# 8OR_1.net
KiCad netlist of a schematic drawn in EAGLE
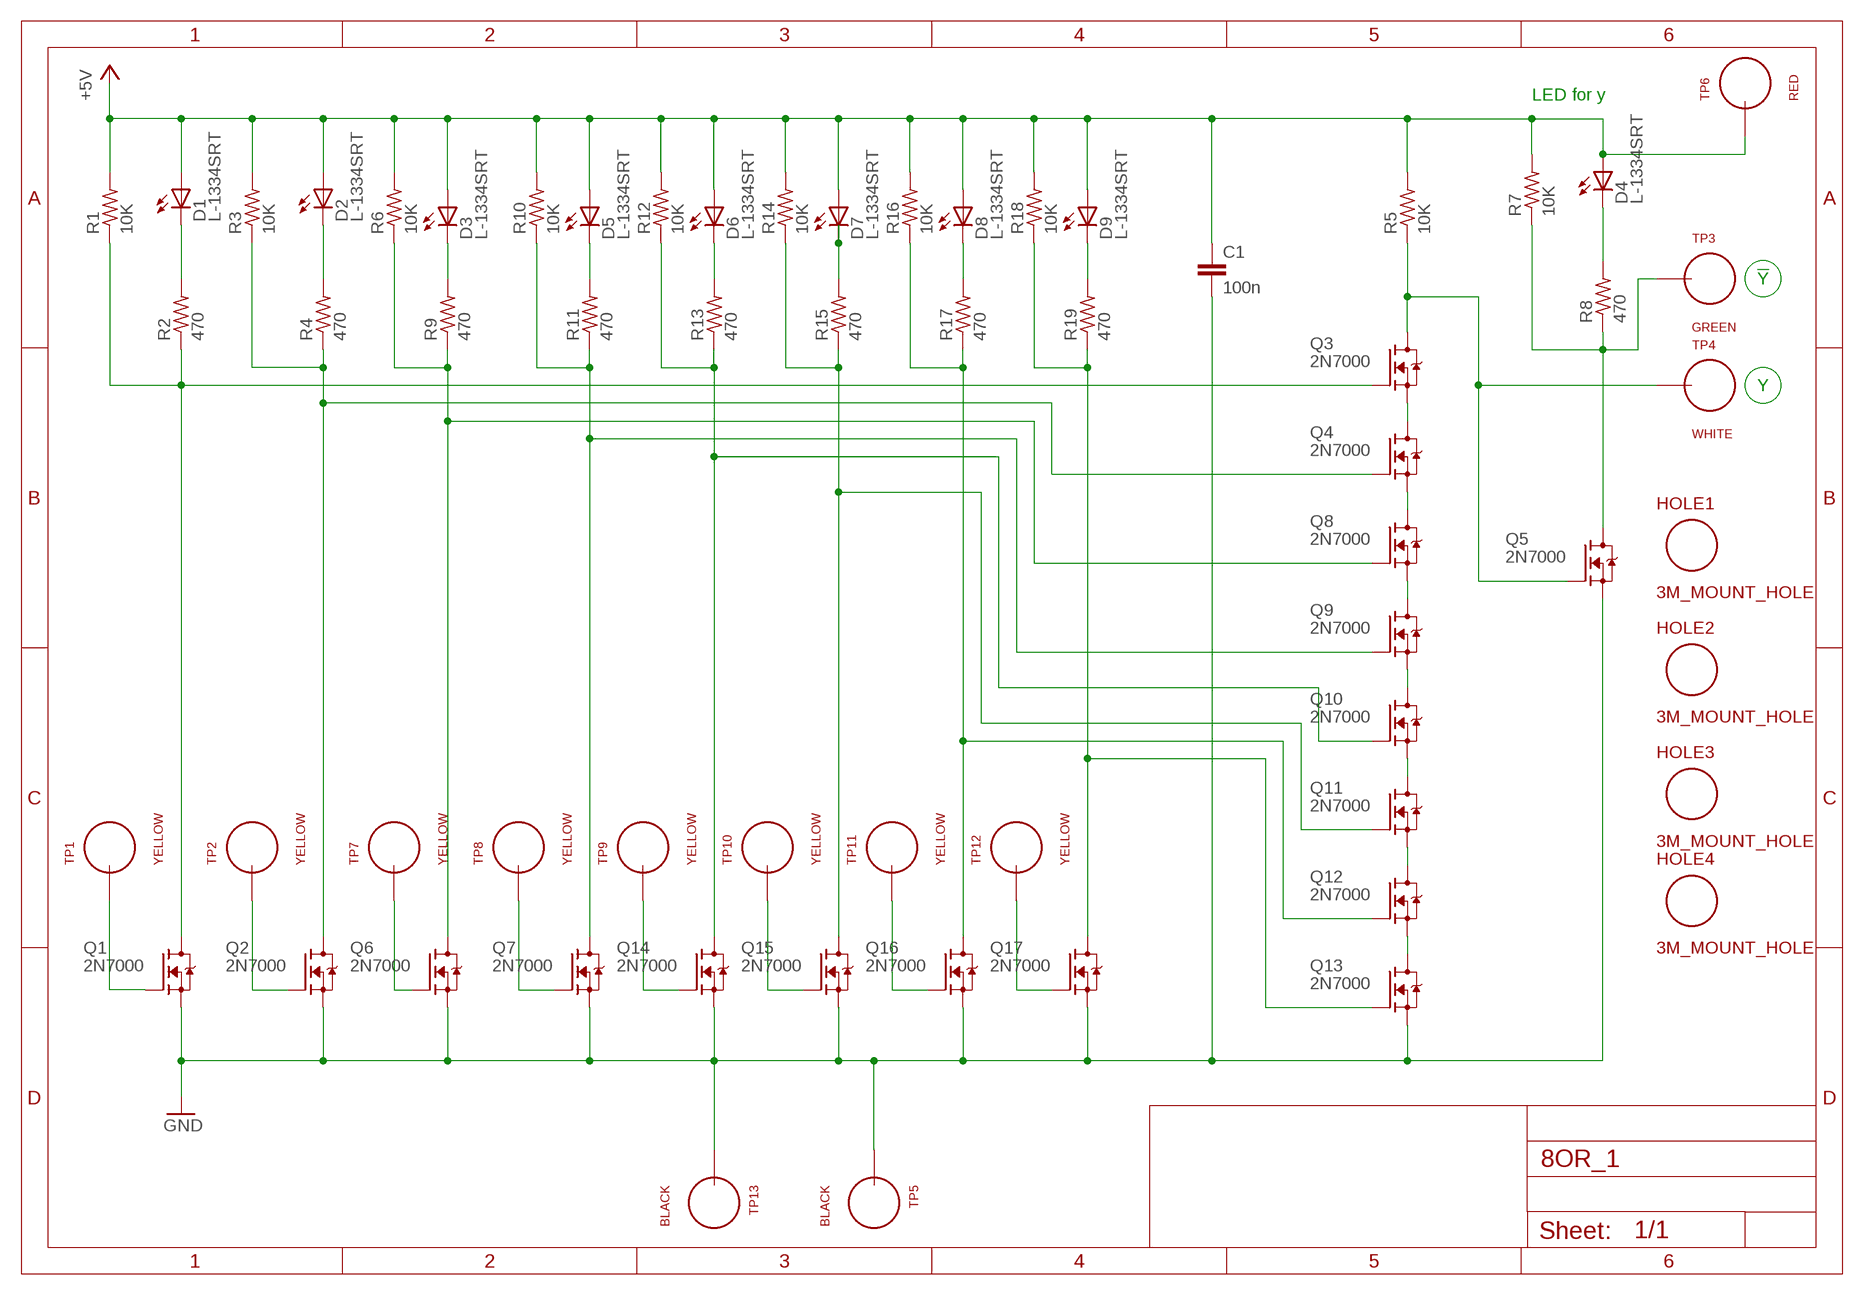
[diagram p0: schematic, sheet 1]

(export (version "E")
  (design (tool "Eeschema 10.0.6"))
  (components
    (comp (ref "C1")
      (value "100n")
      (footprint "eagle-import:CAP_P2INCH")
      (libsource (lib "eagle-import") (part "C_P2INCH"))
    )
    (comp (ref "D1")
      (value "L-1334SRT")
      (footprint "eagle-import:LED3MM")
      (libsource (lib "eagle-import") (part "L-1334SRT"))
    )
    (comp (ref "D2")
      (value "L-1334SRT")
      (footprint "eagle-import:LED3MM")
      (libsource (lib "eagle-import") (part "L-1334SRT"))
    )
    (comp (ref "D3")
      (value "L-1334SRT")
      (footprint "eagle-import:LED3MM")
      (libsource (lib "eagle-import") (part "L-1334SRT"))
    )
    (comp (ref "D4")
      (value "L-1334SRT")
      (footprint "eagle-import:LED3MM")
      (libsource (lib "eagle-import") (part "L-1334SRT"))
    )
    (comp (ref "D5")
      (value "L-1334SRT")
      (footprint "eagle-import:LED3MM")
      (libsource (lib "eagle-import") (part "L-1334SRT"))
    )
    (comp (ref "D6")
      (value "L-1334SRT")
      (footprint "eagle-import:LED3MM")
      (libsource (lib "eagle-import") (part "L-1334SRT"))
    )
    (comp (ref "D7")
      (value "L-1334SRT")
      (footprint "eagle-import:LED3MM")
      (libsource (lib "eagle-import") (part "L-1334SRT"))
    )
    (comp (ref "D8")
      (value "L-1334SRT")
      (footprint "eagle-import:LED3MM")
      (libsource (lib "eagle-import") (part "L-1334SRT"))
    )
    (comp (ref "D9")
      (value "L-1334SRT")
      (footprint "eagle-import:LED3MM")
      (libsource (lib "eagle-import") (part "L-1334SRT"))
    )
    (comp (ref "HOLE1")
      (value "3M_MOUNT_HOLE")
      (footprint "eagle-import:3M_HOLE")
      (libsource (lib "eagle-import") (part "3M_MOUNT_HOLE"))
    )
    (comp (ref "HOLE2")
      (value "3M_MOUNT_HOLE")
      (footprint "eagle-import:3M_HOLE")
      (libsource (lib "eagle-import") (part "3M_MOUNT_HOLE"))
    )
    (comp (ref "HOLE3")
      (value "3M_MOUNT_HOLE")
      (footprint "eagle-import:3M_HOLE")
      (libsource (lib "eagle-import") (part "3M_MOUNT_HOLE"))
    )
    (comp (ref "HOLE4")
      (value "3M_MOUNT_HOLE")
      (footprint "eagle-import:3M_HOLE")
      (libsource (lib "eagle-import") (part "3M_MOUNT_HOLE"))
    )
    (comp (ref "Q1")
      (value "2N7000")
      (footprint "eagle-import:TO92-DGS")
      (libsource (lib "eagle-import") (part "2N7000"))
    )
    (comp (ref "Q2")
      (value "2N7000")
      (footprint "eagle-import:TO92-DGS")
      (libsource (lib "eagle-import") (part "2N7000"))
    )
    (comp (ref "Q3")
      (value "2N7000")
      (footprint "eagle-import:TO92-DGS")
      (libsource (lib "eagle-import") (part "2N7000"))
    )
    (comp (ref "Q4")
      (value "2N7000")
      (footprint "eagle-import:TO92-DGS")
      (libsource (lib "eagle-import") (part "2N7000"))
    )
    (comp (ref "Q5")
      (value "2N7000")
      (footprint "eagle-import:TO92-DGS")
      (libsource (lib "eagle-import") (part "2N7000"))
    )
    (comp (ref "Q6")
      (value "2N7000")
      (footprint "eagle-import:TO92-DGS")
      (libsource (lib "eagle-import") (part "2N7000"))
    )
    (comp (ref "Q7")
      (value "2N7000")
      (footprint "eagle-import:TO92-DGS")
      (libsource (lib "eagle-import") (part "2N7000"))
    )
    (comp (ref "Q8")
      (value "2N7000")
      (footprint "eagle-import:TO92-DGS")
      (libsource (lib "eagle-import") (part "2N7000"))
    )
    (comp (ref "Q9")
      (value "2N7000")
      (footprint "eagle-import:TO92-DGS")
      (libsource (lib "eagle-import") (part "2N7000"))
    )
    (comp (ref "Q10")
      (value "2N7000")
      (footprint "eagle-import:TO92-DGS")
      (libsource (lib "eagle-import") (part "2N7000"))
    )
    (comp (ref "Q11")
      (value "2N7000")
      (footprint "eagle-import:TO92-DGS")
      (libsource (lib "eagle-import") (part "2N7000"))
    )
    (comp (ref "Q12")
      (value "2N7000")
      (footprint "eagle-import:TO92-DGS")
      (libsource (lib "eagle-import") (part "2N7000"))
    )
    (comp (ref "Q13")
      (value "2N7000")
      (footprint "eagle-import:TO92-DGS")
      (libsource (lib "eagle-import") (part "2N7000"))
    )
    (comp (ref "Q14")
      (value "2N7000")
      (footprint "eagle-import:TO92-DGS")
      (libsource (lib "eagle-import") (part "2N7000"))
    )
    (comp (ref "Q15")
      (value "2N7000")
      (footprint "eagle-import:TO92-DGS")
      (libsource (lib "eagle-import") (part "2N7000"))
    )
    (comp (ref "Q16")
      (value "2N7000")
      (footprint "eagle-import:TO92-DGS")
      (libsource (lib "eagle-import") (part "2N7000"))
    )
    (comp (ref "Q17")
      (value "2N7000")
      (footprint "eagle-import:TO92-DGS")
      (libsource (lib "eagle-import") (part "2N7000"))
    )
    (comp (ref "R1")
      (value "10K")
      (footprint "eagle-import:R_P2INCH")
      (libsource (lib "eagle-import") (part "R_P2INCH"))
    )
    (comp (ref "R2")
      (value "470")
      (footprint "eagle-import:R_P2INCH")
      (libsource (lib "eagle-import") (part "R_P2INCH"))
    )
    (comp (ref "R3")
      (value "10K")
      (footprint "eagle-import:R_P2INCH")
      (libsource (lib "eagle-import") (part "R_P2INCH"))
    )
    (comp (ref "R4")
      (value "470")
      (footprint "eagle-import:R_P2INCH")
      (libsource (lib "eagle-import") (part "R_P2INCH"))
    )
    (comp (ref "R5")
      (value "10K")
      (footprint "eagle-import:R_P2INCH")
      (libsource (lib "eagle-import") (part "R_P2INCH"))
    )
    (comp (ref "R6")
      (value "10K")
      (footprint "eagle-import:R_P2INCH")
      (libsource (lib "eagle-import") (part "R_P2INCH"))
    )
    (comp (ref "R7")
      (value "10K")
      (footprint "eagle-import:R_P2INCH")
      (libsource (lib "eagle-import") (part "R_P2INCH"))
    )
    (comp (ref "R8")
      (value "470")
      (footprint "eagle-import:R_P2INCH")
      (libsource (lib "eagle-import") (part "R_P2INCH"))
    )
    (comp (ref "R9")
      (value "470")
      (footprint "eagle-import:R_P2INCH")
      (libsource (lib "eagle-import") (part "R_P2INCH"))
    )
    (comp (ref "R10")
      (value "10K")
      (footprint "eagle-import:R_P2INCH")
      (libsource (lib "eagle-import") (part "R_P2INCH"))
    )
    (comp (ref "R11")
      (value "470")
      (footprint "eagle-import:R_P2INCH")
      (libsource (lib "eagle-import") (part "R_P2INCH"))
    )
    (comp (ref "R12")
      (value "10K")
      (footprint "eagle-import:R_P2INCH")
      (libsource (lib "eagle-import") (part "R_P2INCH"))
    )
    (comp (ref "R13")
      (value "470")
      (footprint "eagle-import:R_P2INCH")
      (libsource (lib "eagle-import") (part "R_P2INCH"))
    )
    (comp (ref "R14")
      (value "10K")
      (footprint "eagle-import:R_P2INCH")
      (libsource (lib "eagle-import") (part "R_P2INCH"))
    )
    (comp (ref "R15")
      (value "470")
      (footprint "eagle-import:R_P2INCH")
      (libsource (lib "eagle-import") (part "R_P2INCH"))
    )
    (comp (ref "R16")
      (value "10K")
      (footprint "eagle-import:R_P2INCH")
      (libsource (lib "eagle-import") (part "R_P2INCH"))
    )
    (comp (ref "R17")
      (value "470")
      (footprint "eagle-import:R_P2INCH")
      (libsource (lib "eagle-import") (part "R_P2INCH"))
    )
    (comp (ref "R18")
      (value "10K")
      (footprint "eagle-import:R_P2INCH")
      (libsource (lib "eagle-import") (part "R_P2INCH"))
    )
    (comp (ref "R19")
      (value "470")
      (footprint "eagle-import:R_P2INCH")
      (libsource (lib "eagle-import") (part "R_P2INCH"))
    )
    (comp (ref "TP1")
      (value "YELLOW")
      (footprint "eagle-import:TEST_LOOP")
      (libsource (lib "eagle-import") (part "TEST_LOOP"))
    )
    (comp (ref "TP2")
      (value "YELLOW")
      (footprint "eagle-import:TEST_LOOP")
      (libsource (lib "eagle-import") (part "TEST_LOOP"))
    )
    (comp (ref "TP3")
      (value "GREEN")
      (footprint "eagle-import:TEST_LOOP")
      (libsource (lib "eagle-import") (part "TEST_LOOP"))
    )
    (comp (ref "TP4")
      (value "WHITE")
      (footprint "eagle-import:TEST_LOOP")
      (libsource (lib "eagle-import") (part "TEST_LOOP"))
    )
    (comp (ref "TP5")
      (value "BLACK")
      (footprint "eagle-import:TEST_LOOP")
      (libsource (lib "eagle-import") (part "TEST_LOOP"))
    )
    (comp (ref "TP6")
      (value "RED")
      (footprint "eagle-import:TEST_LOOP")
      (libsource (lib "eagle-import") (part "TEST_LOOP"))
    )
    (comp (ref "TP7")
      (value "YELLOW")
      (footprint "eagle-import:TEST_LOOP")
      (libsource (lib "eagle-import") (part "TEST_LOOP"))
    )
    (comp (ref "TP8")
      (value "YELLOW")
      (footprint "eagle-import:TEST_LOOP")
      (libsource (lib "eagle-import") (part "TEST_LOOP"))
    )
    (comp (ref "TP9")
      (value "YELLOW")
      (footprint "eagle-import:TEST_LOOP")
      (libsource (lib "eagle-import") (part "TEST_LOOP"))
    )
    (comp (ref "TP10")
      (value "YELLOW")
      (footprint "eagle-import:TEST_LOOP")
      (libsource (lib "eagle-import") (part "TEST_LOOP"))
    )
    (comp (ref "TP11")
      (value "YELLOW")
      (footprint "eagle-import:TEST_LOOP")
      (libsource (lib "eagle-import") (part "TEST_LOOP"))
    )
    (comp (ref "TP12")
      (value "YELLOW")
      (footprint "eagle-import:TEST_LOOP")
      (libsource (lib "eagle-import") (part "TEST_LOOP"))
    )
    (comp (ref "TP13")
      (value "BLACK")
      (footprint "eagle-import:TEST_LOOP")
      (libsource (lib "eagle-import") (part "TEST_LOOP"))
    )
  )
  (nets
    (net (code "1") (name "+5V") (class "Default")
      (node (ref "C1") (pin "1") (pinfunction "1_1") (pintype "passive"))
      (node (ref "D1") (pin "A") (pinfunction "A_A") (pintype "passive"))
      (node (ref "D2") (pin "A") (pinfunction "A_A") (pintype "passive"))
      (node (ref "D3") (pin "A") (pinfunction "A_A") (pintype "passive"))
      (node (ref "D4") (pin "A") (pinfunction "A_A") (pintype "passive"))
      (node (ref "D5") (pin "A") (pinfunction "A_A") (pintype "passive"))
      (node (ref "D6") (pin "A") (pinfunction "A_A") (pintype "passive"))
      (node (ref "D7") (pin "A") (pinfunction "A_A") (pintype "passive"))
      (node (ref "D8") (pin "A") (pinfunction "A_A") (pintype "passive"))
      (node (ref "D9") (pin "A") (pinfunction "A_A") (pintype "passive"))
      (node (ref "R1") (pin "2") (pinfunction "2_2") (pintype "passive"))
      (node (ref "R10") (pin "2") (pinfunction "2_2") (pintype "passive"))
      (node (ref "R12") (pin "2") (pinfunction "2_2") (pintype "passive"))
      (node (ref "R14") (pin "2") (pinfunction "2_2") (pintype "passive"))
      (node (ref "R16") (pin "2") (pinfunction "2_2") (pintype "passive"))
      (node (ref "R18") (pin "2") (pinfunction "2_2") (pintype "passive"))
      (node (ref "R3") (pin "2") (pinfunction "2_2") (pintype "passive"))
      (node (ref "R5") (pin "2") (pinfunction "2_2") (pintype "passive"))
      (node (ref "R6") (pin "2") (pinfunction "2_2") (pintype "passive"))
      (node (ref "R7") (pin "2") (pinfunction "2_2") (pintype "passive"))
      (node (ref "TP6") (pin "P$1") (pinfunction "P$1_P$1") (pintype "bidirectional"))
    )
    (net (code "2") (name "GND") (class "Default")
      (node (ref "C1") (pin "2") (pinfunction "2_2") (pintype "passive"))
      (node (ref "Q1") (pin "S") (pinfunction "S_S") (pintype "passive"))
      (node (ref "Q13") (pin "S") (pinfunction "S_S") (pintype "passive"))
      (node (ref "Q14") (pin "S") (pinfunction "S_S") (pintype "passive"))
      (node (ref "Q15") (pin "S") (pinfunction "S_S") (pintype "passive"))
      (node (ref "Q16") (pin "S") (pinfunction "S_S") (pintype "passive"))
      (node (ref "Q17") (pin "S") (pinfunction "S_S") (pintype "passive"))
      (node (ref "Q2") (pin "S") (pinfunction "S_S") (pintype "passive"))
      (node (ref "Q5") (pin "S") (pinfunction "S_S") (pintype "passive"))
      (node (ref "Q6") (pin "S") (pinfunction "S_S") (pintype "passive"))
      (node (ref "Q7") (pin "S") (pinfunction "S_S") (pintype "passive"))
      (node (ref "TP13") (pin "P$1") (pinfunction "P$1_P$1") (pintype "bidirectional"))
      (node (ref "TP5") (pin "P$1") (pinfunction "P$1_P$1") (pintype "bidirectional"))
    )
    (net (code "3") (name "Net-(D1-C)") (class "Default")
      (node (ref "D1") (pin "K") (pinfunction "C_K") (pintype "passive"))
      (node (ref "R2") (pin "2") (pinfunction "2_2") (pintype "passive"))
    )
    (net (code "4") (name "Net-(D2-C)") (class "Default")
      (node (ref "D2") (pin "K") (pinfunction "C_K") (pintype "passive"))
      (node (ref "R4") (pin "2") (pinfunction "2_2") (pintype "passive"))
    )
    (net (code "5") (name "Net-(D3-C)") (class "Default")
      (node (ref "D3") (pin "K") (pinfunction "C_K") (pintype "passive"))
      (node (ref "R9") (pin "2") (pinfunction "2_2") (pintype "passive"))
    )
    (net (code "6") (name "Net-(D4-C)") (class "Default")
      (node (ref "D4") (pin "K") (pinfunction "C_K") (pintype "passive"))
      (node (ref "R8") (pin "2") (pinfunction "2_2") (pintype "passive"))
    )
    (net (code "7") (name "Net-(D5-C)") (class "Default")
      (node (ref "D5") (pin "K") (pinfunction "C_K") (pintype "passive"))
      (node (ref "R11") (pin "2") (pinfunction "2_2") (pintype "passive"))
    )
    (net (code "8") (name "Net-(D6-C)") (class "Default")
      (node (ref "D6") (pin "K") (pinfunction "C_K") (pintype "passive"))
      (node (ref "R13") (pin "2") (pinfunction "2_2") (pintype "passive"))
    )
    (net (code "9") (name "Net-(D7-C)") (class "Default")
      (node (ref "D7") (pin "K") (pinfunction "C_K") (pintype "passive"))
      (node (ref "R15") (pin "2") (pinfunction "2_2") (pintype "passive"))
    )
    (net (code "10") (name "Net-(D8-C)") (class "Default")
      (node (ref "D8") (pin "K") (pinfunction "C_K") (pintype "passive"))
      (node (ref "R17") (pin "2") (pinfunction "2_2") (pintype "passive"))
    )
    (net (code "11") (name "Net-(D9-C)") (class "Default")
      (node (ref "D9") (pin "K") (pinfunction "C_K") (pintype "passive"))
      (node (ref "R19") (pin "2") (pinfunction "2_2") (pintype "passive"))
    )
    (net (code "12") (name "Net-(Q1-PadD)") (class "Default")
      (node (ref "Q1") (pin "D") (pinfunction "D_D") (pintype "passive"))
      (node (ref "Q3") (pin "G") (pinfunction "G_G") (pintype "passive"))
      (node (ref "R1") (pin "1") (pinfunction "1_1") (pintype "passive"))
      (node (ref "R2") (pin "1") (pinfunction "1_1") (pintype "passive"))
    )
    (net (code "13") (name "Net-(Q1-PadG)") (class "Default")
      (node (ref "Q1") (pin "G") (pinfunction "G_G") (pintype "passive"))
      (node (ref "TP1") (pin "P$1") (pinfunction "P$1_P$1") (pintype "bidirectional"))
    )
    (net (code "14") (name "Net-(Q2-PadD)") (class "Default")
      (node (ref "Q2") (pin "D") (pinfunction "D_D") (pintype "passive"))
      (node (ref "Q4") (pin "G") (pinfunction "G_G") (pintype "passive"))
      (node (ref "R3") (pin "1") (pinfunction "1_1") (pintype "passive"))
      (node (ref "R4") (pin "1") (pinfunction "1_1") (pintype "passive"))
    )
    (net (code "15") (name "Net-(Q2-PadG)") (class "Default")
      (node (ref "Q2") (pin "G") (pinfunction "G_G") (pintype "passive"))
      (node (ref "TP2") (pin "P$1") (pinfunction "P$1_P$1") (pintype "bidirectional"))
    )
    (net (code "16") (name "Net-(Q3-PadD)") (class "Default")
      (node (ref "Q3") (pin "D") (pinfunction "D_D") (pintype "passive"))
      (node (ref "Q5") (pin "G") (pinfunction "G_G") (pintype "passive"))
      (node (ref "R5") (pin "1") (pinfunction "1_1") (pintype "passive"))
      (node (ref "TP4") (pin "P$1") (pinfunction "P$1_P$1") (pintype "bidirectional"))
    )
    (net (code "17") (name "Net-(Q3-PadS)") (class "Default")
      (node (ref "Q3") (pin "S") (pinfunction "S_S") (pintype "passive"))
      (node (ref "Q4") (pin "D") (pinfunction "D_D") (pintype "passive"))
    )
    (net (code "18") (name "Net-(Q4-PadS)") (class "Default")
      (node (ref "Q4") (pin "S") (pinfunction "S_S") (pintype "passive"))
      (node (ref "Q8") (pin "D") (pinfunction "D_D") (pintype "passive"))
    )
    (net (code "19") (name "Net-(Q5-PadD)") (class "Default")
      (node (ref "Q5") (pin "D") (pinfunction "D_D") (pintype "passive"))
      (node (ref "R7") (pin "1") (pinfunction "1_1") (pintype "passive"))
      (node (ref "R8") (pin "1") (pinfunction "1_1") (pintype "passive"))
      (node (ref "TP3") (pin "P$1") (pinfunction "P$1_P$1") (pintype "bidirectional"))
    )
    (net (code "20") (name "Net-(Q6-PadD)") (class "Default")
      (node (ref "Q6") (pin "D") (pinfunction "D_D") (pintype "passive"))
      (node (ref "Q8") (pin "G") (pinfunction "G_G") (pintype "passive"))
      (node (ref "R6") (pin "1") (pinfunction "1_1") (pintype "passive"))
      (node (ref "R9") (pin "1") (pinfunction "1_1") (pintype "passive"))
    )
    (net (code "21") (name "Net-(Q6-PadG)") (class "Default")
      (node (ref "Q6") (pin "G") (pinfunction "G_G") (pintype "passive"))
      (node (ref "TP7") (pin "P$1") (pinfunction "P$1_P$1") (pintype "bidirectional"))
    )
    (net (code "22") (name "Net-(Q7-PadD)") (class "Default")
      (node (ref "Q7") (pin "D") (pinfunction "D_D") (pintype "passive"))
      (node (ref "Q9") (pin "G") (pinfunction "G_G") (pintype "passive"))
      (node (ref "R10") (pin "1") (pinfunction "1_1") (pintype "passive"))
      (node (ref "R11") (pin "1") (pinfunction "1_1") (pintype "passive"))
    )
    (net (code "23") (name "Net-(Q7-PadG)") (class "Default")
      (node (ref "Q7") (pin "G") (pinfunction "G_G") (pintype "passive"))
      (node (ref "TP8") (pin "P$1") (pinfunction "P$1_P$1") (pintype "bidirectional"))
    )
    (net (code "24") (name "Net-(Q8-PadS)") (class "Default")
      (node (ref "Q8") (pin "S") (pinfunction "S_S") (pintype "passive"))
      (node (ref "Q9") (pin "D") (pinfunction "D_D") (pintype "passive"))
    )
    (net (code "25") (name "Net-(Q10-PadD)") (class "Default")
      (node (ref "Q10") (pin "D") (pinfunction "D_D") (pintype "passive"))
      (node (ref "Q9") (pin "S") (pinfunction "S_S") (pintype "passive"))
    )
    (net (code "26") (name "Net-(Q10-PadG)") (class "Default")
      (node (ref "Q10") (pin "G") (pinfunction "G_G") (pintype "passive"))
      (node (ref "Q14") (pin "D") (pinfunction "D_D") (pintype "passive"))
      (node (ref "R12") (pin "1") (pinfunction "1_1") (pintype "passive"))
      (node (ref "R13") (pin "1") (pinfunction "1_1") (pintype "passive"))
    )
    (net (code "27") (name "Net-(Q10-PadS)") (class "Default")
      (node (ref "Q10") (pin "S") (pinfunction "S_S") (pintype "passive"))
      (node (ref "Q11") (pin "D") (pinfunction "D_D") (pintype "passive"))
    )
    (net (code "28") (name "Net-(Q11-PadG)") (class "Default")
      (node (ref "Q11") (pin "G") (pinfunction "G_G") (pintype "passive"))
      (node (ref "Q15") (pin "D") (pinfunction "D_D") (pintype "passive"))
      (node (ref "R14") (pin "1") (pinfunction "1_1") (pintype "passive"))
      (node (ref "R15") (pin "1") (pinfunction "1_1") (pintype "passive"))
    )
    (net (code "29") (name "Net-(Q11-PadS)") (class "Default")
      (node (ref "Q11") (pin "S") (pinfunction "S_S") (pintype "passive"))
      (node (ref "Q12") (pin "D") (pinfunction "D_D") (pintype "passive"))
    )
    (net (code "30") (name "Net-(Q12-PadG)") (class "Default")
      (node (ref "Q12") (pin "G") (pinfunction "G_G") (pintype "passive"))
      (node (ref "Q16") (pin "D") (pinfunction "D_D") (pintype "passive"))
      (node (ref "R16") (pin "1") (pinfunction "1_1") (pintype "passive"))
      (node (ref "R17") (pin "1") (pinfunction "1_1") (pintype "passive"))
    )
    (net (code "31") (name "Net-(Q12-PadS)") (class "Default")
      (node (ref "Q12") (pin "S") (pinfunction "S_S") (pintype "passive"))
      (node (ref "Q13") (pin "D") (pinfunction "D_D") (pintype "passive"))
    )
    (net (code "32") (name "Net-(Q13-PadG)") (class "Default")
      (node (ref "Q13") (pin "G") (pinfunction "G_G") (pintype "passive"))
      (node (ref "Q17") (pin "D") (pinfunction "D_D") (pintype "passive"))
      (node (ref "R18") (pin "1") (pinfunction "1_1") (pintype "passive"))
      (node (ref "R19") (pin "1") (pinfunction "1_1") (pintype "passive"))
    )
    (net (code "33") (name "Net-(Q14-PadG)") (class "Default")
      (node (ref "Q14") (pin "G") (pinfunction "G_G") (pintype "passive"))
      (node (ref "TP9") (pin "P$1") (pinfunction "P$1_P$1") (pintype "bidirectional"))
    )
    (net (code "34") (name "Net-(Q15-PadG)") (class "Default")
      (node (ref "Q15") (pin "G") (pinfunction "G_G") (pintype "passive"))
      (node (ref "TP10") (pin "P$1") (pinfunction "P$1_P$1") (pintype "bidirectional"))
    )
    (net (code "35") (name "Net-(Q16-PadG)") (class "Default")
      (node (ref "Q16") (pin "G") (pinfunction "G_G") (pintype "passive"))
      (node (ref "TP11") (pin "P$1") (pinfunction "P$1_P$1") (pintype "bidirectional"))
    )
    (net (code "36") (name "Net-(Q17-PadG)") (class "Default")
      (node (ref "Q17") (pin "G") (pinfunction "G_G") (pintype "passive"))
      (node (ref "TP12") (pin "P$1") (pinfunction "P$1_P$1") (pintype "bidirectional"))
    )
  )
)
